# YL.net
KiCad netlist of a schematic drawn in Altium Designer
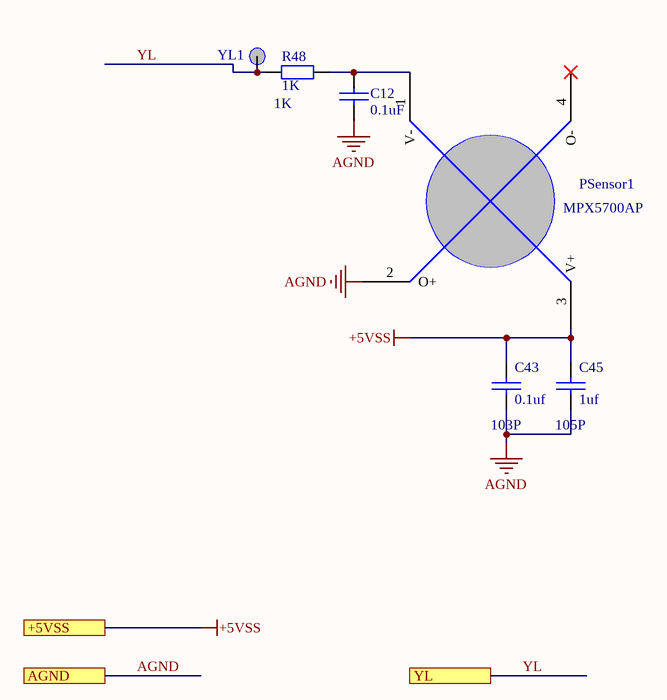
[diagram p0: YL.SchDoc]

(export (version "E")
  (design (tool "Eeschema 10.0.6"))
  (components
    (comp (ref "C12") (value "0.1uF") (footprint "0805C") (libsource (lib "") (part "CAP_1")))
    (comp (ref "C43")
      (value "0.1uf")
      (footprint "0805C")
      (description "Capacitor")
      (fields (field (name "ALTIUM_VALUE") "103P"))
      (libsource (lib "*") (part "CAP"))
    )
    (comp (ref "C45")
      (value "1uf")
      (footprint "0805C")
      (description "Capacitor")
      (fields (field (name "ALTIUM_VALUE") "105P"))
      (libsource (lib "*") (part "CAP"))
    )
    (comp (ref "PSensor1") (value "MPX5700AP") (footprint "MPX5700AP") (libsource (lib "*") (part "MPX")))
    (comp (ref "R48")
      (value "1K")
      (footprint "0805R")
      (description "Resistor")
      (fields
        (field (name "MANUFACTURER") "Generic Components")
        (field (name "ALTIUM_VALUE") "1K")
        (field (name "PUBLISHER") "Altium Hobart Technology Centre")
      )
      (libsource (lib "*") (part "RES2"))
    )
    (comp (ref "YL1") (value "~") (footprint "TPP") (libsource (lib "*") (part "TP")))
  )
  (nets
    (net (code "1") (name "+5VSS") (class "Default")
      (node (ref "C43") (pin "1") (pinfunction "1_1") (pintype "passive"))
      (node (ref "C45") (pin "2") (pinfunction "2_2") (pintype "passive"))
      (node (ref "PSensor1") (pin "3") (pinfunction "V+_3") (pintype "passive"))
    )
    (net (code "2") (name "/YL") (class "Default")
      (node (ref "R48") (pin "2") (pinfunction "2_2") (pintype "passive"))
      (node (ref "YL1") (pin "1") (pinfunction "1_1") (pintype "passive"))
    )
    (net (code "3") (name "AGND") (class "Default")
      (node (ref "C12") (pin "2") (pintype "passive"))
      (node (ref "C43") (pin "2") (pinfunction "2_2") (pintype "passive"))
      (node (ref "C45") (pin "1") (pinfunction "1_1") (pintype "passive"))
      (node (ref "PSensor1") (pin "2") (pinfunction "O+_2") (pintype "passive"))
    )
    (net (code "4") (name "Net-(PSensor1-V-)") (class "Default")
      (node (ref "C12") (pin "1") (pintype "passive"))
      (node (ref "PSensor1") (pin "1") (pinfunction "V-_1") (pintype "passive"))
      (node (ref "R48") (pin "1") (pinfunction "1_1") (pintype "passive"))
    )
    (net (code "5") (name "unconnected-(PSensor1-O--Pad4)") (class "Default")
      (node (ref "PSensor1") (pin "4") (pinfunction "O-_4") (pintype "passive+no_connect"))
    )
  )
)
